# Coil_sensor_board.net
KiCad netlist of a schematic drawn in EAGLE
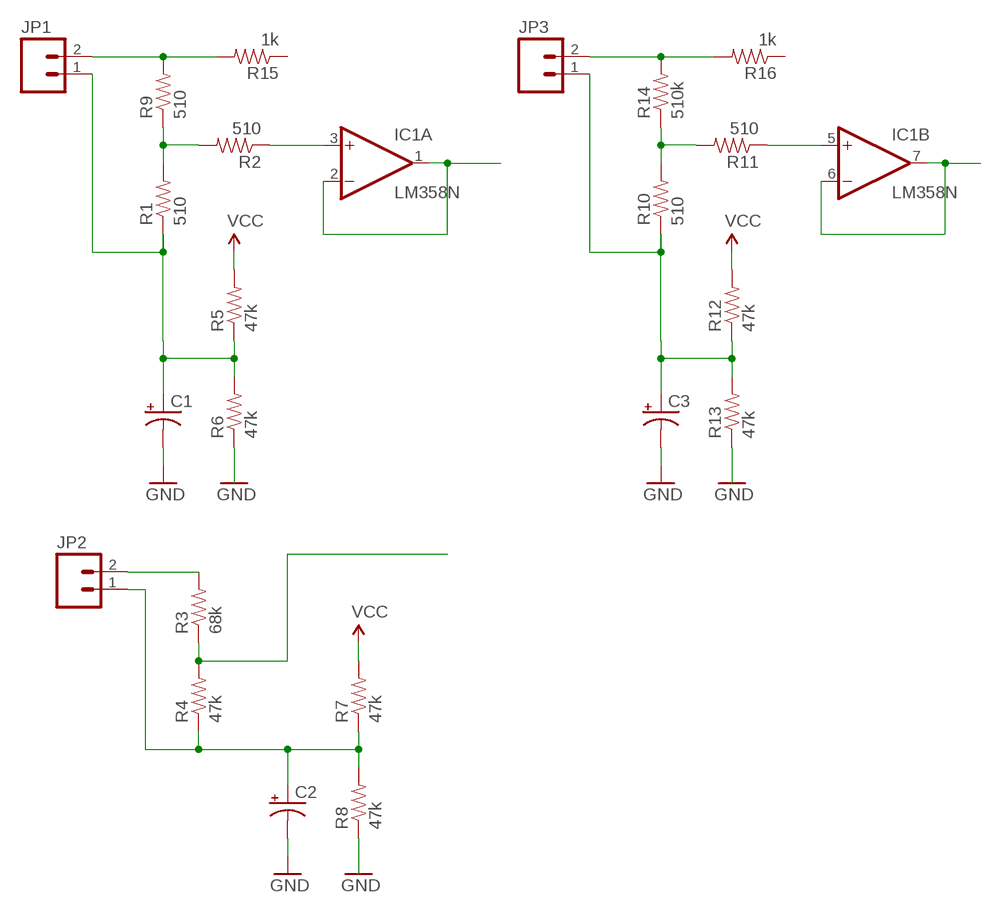
[diagram p0: schematic, sheet 1]

(export (version "E")
  (design (tool "Eeschema 10.0.6"))
  (components
    (comp (ref "C1")
      (value "CAP_POLPTH1")
      (footprint "eagle-import:CPOL-RADIAL-100UF-25V")
      (libsource (lib "eagle-import") (part "CAP_POLPTH1"))
    )
    (comp (ref "C2")
      (value "CAP_POLPTH1")
      (footprint "eagle-import:CPOL-RADIAL-100UF-25V")
      (libsource (lib "eagle-import") (part "CAP_POLPTH1"))
    )
    (comp (ref "C3")
      (value "CAP_POLPTH1")
      (footprint "eagle-import:CPOL-RADIAL-100UF-25V")
      (libsource (lib "eagle-import") (part "CAP_POLPTH1"))
    )
    (comp (ref "IC1")
      (value "LM358N")
      (footprint "eagle-import:DIL08")
      (libsource (lib "eagle-import") (part "LM358N"))
    )
    (comp (ref "JP1")
      (value "M02PTH")
      (footprint "eagle-import:1X02")
      (libsource (lib "eagle-import") (part "M02PTH"))
    )
    (comp (ref "JP2")
      (value "M02PTH")
      (footprint "eagle-import:1X02")
      (libsource (lib "eagle-import") (part "M02PTH"))
    )
    (comp (ref "JP3")
      (value "M02PTH")
      (footprint "eagle-import:1X02")
      (libsource (lib "eagle-import") (part "M02PTH"))
    )
    (comp (ref "R1")
      (value "510")
      (footprint "eagle-import:1_6W-RES")
      (libsource (lib "eagle-import") (part "RESISTORPTH-1/6W"))
    )
    (comp (ref "R2")
      (value "510")
      (footprint "eagle-import:1_6W-RES")
      (libsource (lib "eagle-import") (part "RESISTORPTH-1/6W"))
    )
    (comp (ref "R3")
      (value "68k")
      (footprint "eagle-import:1_6W-RES")
      (libsource (lib "eagle-import") (part "RESISTORPTH-1/6W"))
    )
    (comp (ref "R4")
      (value "47k")
      (footprint "eagle-import:1_6W-RES")
      (libsource (lib "eagle-import") (part "RESISTORPTH-1/6W"))
    )
    (comp (ref "R5")
      (value "47k")
      (footprint "eagle-import:1_6W-RES")
      (libsource (lib "eagle-import") (part "RESISTORPTH-1/6W"))
    )
    (comp (ref "R6")
      (value "47k")
      (footprint "eagle-import:1_6W-RES")
      (libsource (lib "eagle-import") (part "RESISTORPTH-1/6W"))
    )
    (comp (ref "R7")
      (value "47k")
      (footprint "eagle-import:1_6W-RES")
      (libsource (lib "eagle-import") (part "RESISTORPTH-1/6W"))
    )
    (comp (ref "R8")
      (value "47k")
      (footprint "eagle-import:1_6W-RES")
      (libsource (lib "eagle-import") (part "RESISTORPTH-1/6W"))
    )
    (comp (ref "R9")
      (value "510")
      (footprint "eagle-import:1_6W-RES")
      (libsource (lib "eagle-import") (part "RESISTORPTH-1/6W"))
    )
    (comp (ref "R10")
      (value "510")
      (footprint "eagle-import:1_6W-RES")
      (libsource (lib "eagle-import") (part "RESISTORPTH-1/6W"))
    )
    (comp (ref "R11")
      (value "510")
      (footprint "eagle-import:1_6W-RES")
      (libsource (lib "eagle-import") (part "RESISTORPTH-1/6W"))
    )
    (comp (ref "R12")
      (value "47k")
      (footprint "eagle-import:1_6W-RES")
      (libsource (lib "eagle-import") (part "RESISTORPTH-1/6W"))
    )
    (comp (ref "R13")
      (value "47k")
      (footprint "eagle-import:1_6W-RES")
      (libsource (lib "eagle-import") (part "RESISTORPTH-1/6W"))
    )
    (comp (ref "R14")
      (value "510k")
      (footprint "eagle-import:1_6W-RES")
      (libsource (lib "eagle-import") (part "RESISTORPTH-1/6W"))
    )
    (comp (ref "R15")
      (value "1k")
      (footprint "eagle-import:1_6W-RES")
      (libsource (lib "eagle-import") (part "RESISTORPTH-1/6W"))
    )
    (comp (ref "R16")
      (value "1k")
      (footprint "eagle-import:1_6W-RES")
      (libsource (lib "eagle-import") (part "RESISTORPTH-1/6W"))
    )
  )
  (nets
    (net (code "1") (name "GND") (class "Default")
      (node (ref "C1") (pin "2") (pinfunction "-_2") (pintype "passive"))
      (node (ref "C2") (pin "2") (pinfunction "-_2") (pintype "passive"))
      (node (ref "C3") (pin "2") (pinfunction "-_2") (pintype "passive"))
      (node (ref "R13") (pin "1") (pinfunction "1_1") (pintype "passive"))
      (node (ref "R6") (pin "1") (pinfunction "1_1") (pintype "passive"))
      (node (ref "R8") (pin "1") (pinfunction "1_1") (pintype "passive"))
    )
    (net (code "2") (name "Net-(C1-+)") (class "Default")
      (node (ref "C1") (pin "1") (pinfunction "+_1") (pintype "passive"))
      (node (ref "JP1") (pin "1") (pinfunction "1_1") (pintype "passive"))
      (node (ref "R1") (pin "1") (pinfunction "1_1") (pintype "passive"))
      (node (ref "R5") (pin "1") (pinfunction "1_1") (pintype "passive"))
      (node (ref "R6") (pin "2") (pinfunction "2_2") (pintype "passive"))
    )
    (net (code "3") (name "Net-(C2-+)") (class "Default")
      (node (ref "C2") (pin "1") (pinfunction "+_1") (pintype "passive"))
      (node (ref "JP2") (pin "1") (pinfunction "1_1") (pintype "passive"))
      (node (ref "R4") (pin "1") (pinfunction "1_1") (pintype "passive"))
      (node (ref "R7") (pin "1") (pinfunction "1_1") (pintype "passive"))
      (node (ref "R8") (pin "2") (pinfunction "2_2") (pintype "passive"))
    )
    (net (code "4") (name "Net-(C3-+)") (class "Default")
      (node (ref "C3") (pin "1") (pinfunction "+_1") (pintype "passive"))
      (node (ref "JP3") (pin "1") (pinfunction "1_1") (pintype "passive"))
      (node (ref "R10") (pin "1") (pinfunction "1_1") (pintype "passive"))
      (node (ref "R12") (pin "1") (pinfunction "1_1") (pintype "passive"))
      (node (ref "R13") (pin "2") (pinfunction "2_2") (pintype "passive"))
    )
    (net (code "5") (name "Net-(IC1A-+IN)") (class "Default")
      (node (ref "IC1") (pin "3") (pinfunction "+IN_3") (pintype "input"))
      (node (ref "R2") (pin "1") (pinfunction "1_1") (pintype "passive"))
    )
    (net (code "6") (name "Net-(IC1A--IN)") (class "Default")
      (node (ref "IC1") (pin "1") (pinfunction "OUT_1") (pintype "output"))
      (node (ref "IC1") (pin "2") (pinfunction "-IN_2") (pintype "input"))
    )
    (net (code "7") (name "Net-(IC1B-+IN)") (class "Default")
      (node (ref "IC1") (pin "5") (pinfunction "+IN_5") (pintype "input"))
      (node (ref "R11") (pin "1") (pinfunction "1_1") (pintype "passive"))
    )
    (net (code "8") (name "Net-(IC1B--IN)") (class "Default")
      (node (ref "IC1") (pin "6") (pinfunction "-IN_6") (pintype "input"))
      (node (ref "IC1") (pin "7") (pinfunction "OUT_7") (pintype "output"))
    )
    (net (code "9") (name "Net-(JP1-Pad2)") (class "Default")
      (node (ref "JP1") (pin "2") (pinfunction "2_2") (pintype "passive"))
      (node (ref "R15") (pin "2") (pinfunction "2_2") (pintype "passive"))
      (node (ref "R9") (pin "2") (pinfunction "2_2") (pintype "passive"))
    )
    (net (code "10") (name "Net-(JP2-Pad2)") (class "Default")
      (node (ref "JP2") (pin "2") (pinfunction "2_2") (pintype "passive"))
      (node (ref "R3") (pin "2") (pinfunction "2_2") (pintype "passive"))
    )
    (net (code "11") (name "Net-(JP3-Pad2)") (class "Default")
      (node (ref "JP3") (pin "2") (pinfunction "2_2") (pintype "passive"))
      (node (ref "R14") (pin "2") (pinfunction "2_2") (pintype "passive"))
      (node (ref "R16") (pin "2") (pinfunction "2_2") (pintype "passive"))
    )
    (net (code "12") (name "Net-(R1-Pad2)") (class "Default")
      (node (ref "R1") (pin "2") (pinfunction "2_2") (pintype "passive"))
      (node (ref "R2") (pin "2") (pinfunction "2_2") (pintype "passive"))
      (node (ref "R9") (pin "1") (pinfunction "1_1") (pintype "passive"))
    )
    (net (code "13") (name "Net-(R3-Pad1)") (class "Default")
      (node (ref "R3") (pin "1") (pinfunction "1_1") (pintype "passive"))
      (node (ref "R4") (pin "2") (pinfunction "2_2") (pintype "passive"))
    )
    (net (code "14") (name "Net-(R10-Pad2)") (class "Default")
      (node (ref "R10") (pin "2") (pinfunction "2_2") (pintype "passive"))
      (node (ref "R11") (pin "2") (pinfunction "2_2") (pintype "passive"))
      (node (ref "R14") (pin "1") (pinfunction "1_1") (pintype "passive"))
    )
    (net (code "15") (name "VCC") (class "Default")
      (node (ref "R12") (pin "2") (pinfunction "2_2") (pintype "passive"))
      (node (ref "R5") (pin "2") (pinfunction "2_2") (pintype "passive"))
      (node (ref "R7") (pin "2") (pinfunction "2_2") (pintype "passive"))
    )
    (net (code "16") (name "unconnected-(R15-Pad1)") (class "Default")
      (node (ref "R15") (pin "1") (pinfunction "1_1") (pintype "passive"))
    )
    (net (code "17") (name "unconnected-(R16-Pad1)") (class "Default")
      (node (ref "R16") (pin "1") (pinfunction "1_1") (pintype "passive"))
    )
  )
)
